# Sheet1.net
KiCad netlist of a schematic drawn in Altium Designer
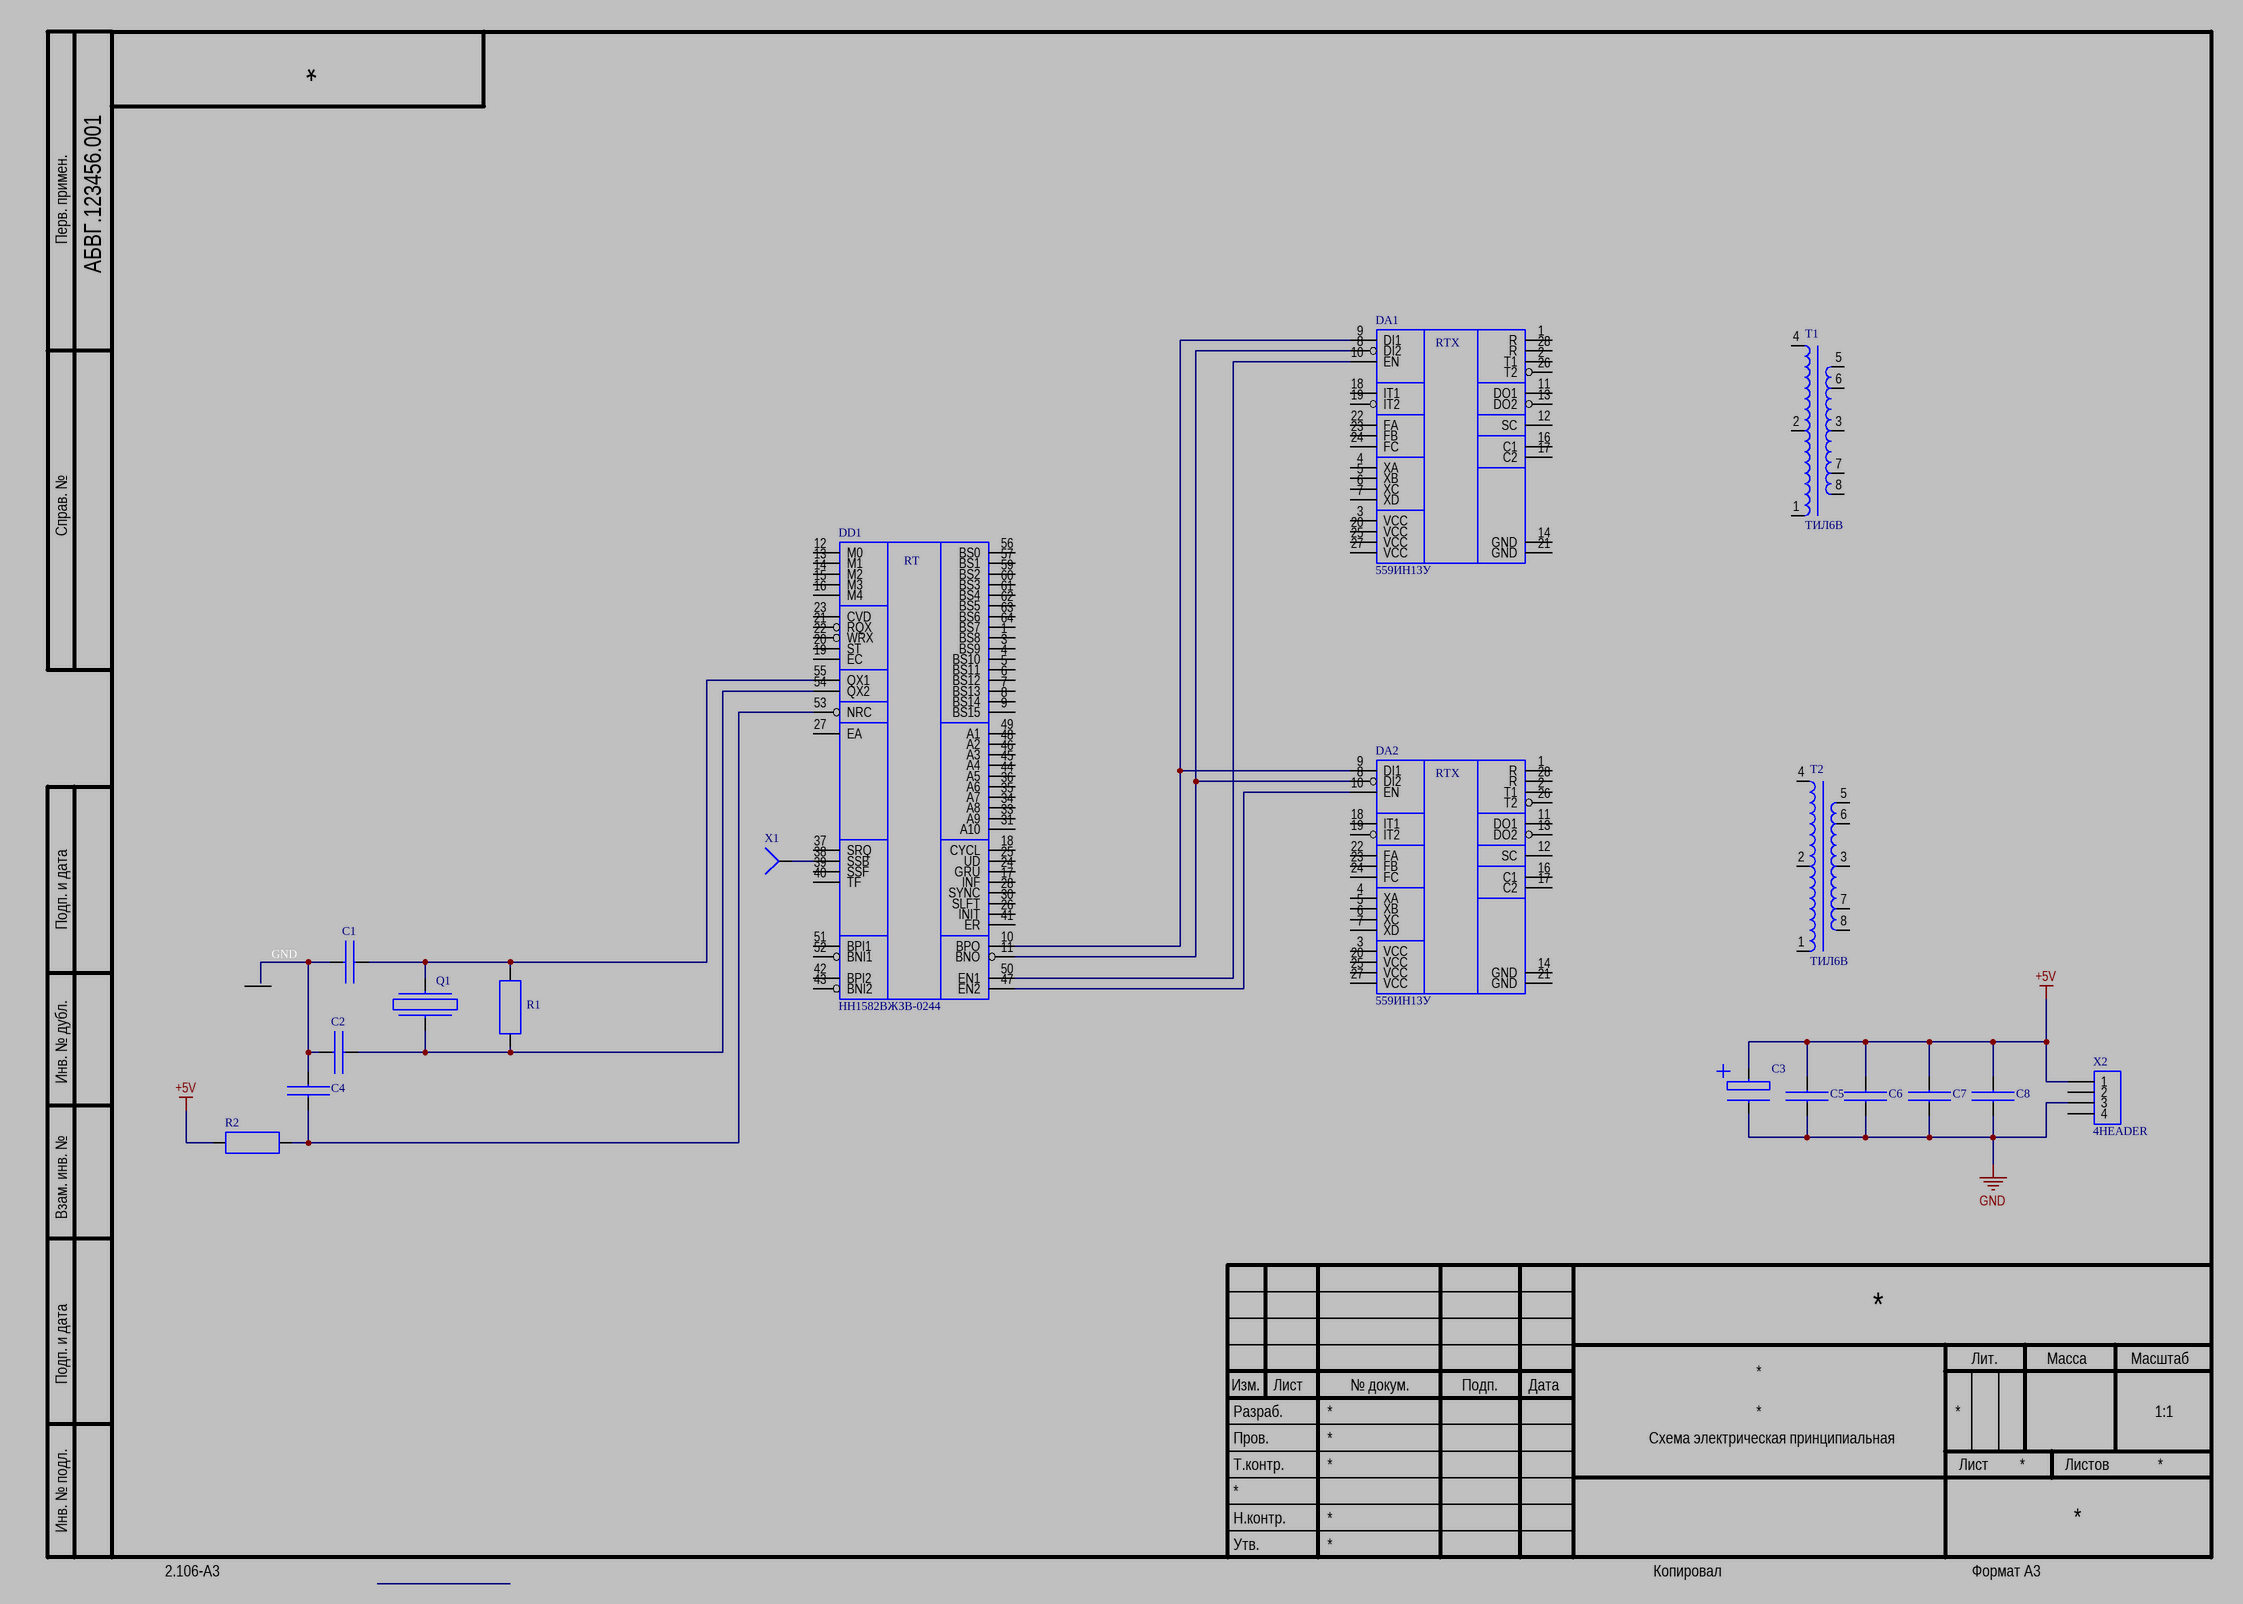
[diagram p0: Sheet1.SchDoc]

(export (version "E")
  (design (tool "Eeschema 10.0.6"))
  (components
    (comp (ref "C1") (value "C_2") (libsource (lib "Schlib1") (part "C_2")))
    (comp (ref "C2") (value "C_2") (libsource (lib "Schlib1") (part "C_2")))
    (comp (ref "C3") (value "C_3") (libsource (lib "Schlib1") (part "C_3")))
    (comp (ref "C4") (value "C_2") (libsource (lib "Schlib1") (part "C_2")))
    (comp (ref "C5") (value "C_2") (libsource (lib "Schlib1") (part "C_2")))
    (comp (ref "C6") (value "C_2") (libsource (lib "Schlib1") (part "C_2")))
    (comp (ref "C7") (value "C_2") (libsource (lib "Schlib1") (part "C_2")))
    (comp (ref "C8") (value "C_2") (libsource (lib "Schlib1") (part "C_2")))
    (comp (ref "DA1")
      (value "559ИН13У")
      (footprint "PcbLib1:H09.28-1B")
      (libsource (lib "Schlib1") (part "559ИН13У"))
    )
    (comp (ref "DA2")
      (value "559ИН13У")
      (footprint "PcbLib1:H09.28-1B")
      (libsource (lib "Schlib1") (part "559ИН13У"))
    )
    (comp (ref "DD1")
      (value "НН1582ВЖЗВ-0244")
      (footprint "PcbLib1:H18.64-1B")
      (libsource (lib "Schlib1") (part "НН1582ВЖЗВ-0244"))
    )
    (comp (ref "Q1") (value "Q_1") (libsource (lib "Schlib1") (part "Q_1")))
    (comp (ref "R1") (value "R_1") (libsource (lib "Schlib1") (part "R_1")))
    (comp (ref "R2") (value "100k") (libsource (lib "Schlib1") (part "R_1")))
    (comp (ref "T1") (value "ТИЛ6B") (libsource (lib "Schlib1") (part "ТИЛ6B")))
    (comp (ref "T2") (value "ТИЛ6B") (libsource (lib "Schlib1") (part "ТИЛ6B")))
    (comp (ref "X1") (value "X_5") (libsource (lib "Schlib1") (part "X_5")))
    (comp (ref "X2") (value "4HEADER") (libsource (lib "Schlib1") (part "4HEADER")))
  )
  (nets
    (net (code "1") (name "+5V") (class "Default")
      (node (ref "C3") (pin "1") (pintype "passive"))
      (node (ref "C5") (pin "2") (pintype "passive"))
      (node (ref "C6") (pin "2") (pintype "passive"))
      (node (ref "C7") (pin "2") (pintype "passive"))
      (node (ref "C8") (pin "2") (pintype "passive"))
      (node (ref "R2") (pin "1") (pintype "passive"))
      (node (ref "X2") (pin "1") (pinfunction "1_1") (pintype "passive"))
    )
    (net (code "2") (name "GND") (class "Default")
      (node (ref "C1") (pin "1") (pintype "passive"))
      (node (ref "C2") (pin "1") (pintype "passive"))
      (node (ref "C3") (pin "2") (pintype "passive"))
      (node (ref "C4") (pin "2") (pintype "passive"))
      (node (ref "C5") (pin "1") (pintype "passive"))
      (node (ref "C6") (pin "1") (pintype "passive"))
      (node (ref "C7") (pin "1") (pintype "passive"))
      (node (ref "C8") (pin "1") (pintype "passive"))
      (node (ref "X2") (pin "3") (pinfunction "3_3") (pintype "passive"))
    )
    (net (code "3") (name "Net-(DA1-DI1)") (class "Default")
      (node (ref "DA1") (pin "9") (pinfunction "DI1_9") (pintype "passive"))
      (node (ref "DA2") (pin "9") (pinfunction "DI1_9") (pintype "passive"))
      (node (ref "DD1") (pin "10") (pinfunction "BPO_10") (pintype "passive"))
    )
    (net (code "4") (name "Net-(DA1-DI2)") (class "Default")
      (node (ref "DA1") (pin "8") (pinfunction "DI2_8") (pintype "passive"))
      (node (ref "DA2") (pin "8") (pinfunction "DI2_8") (pintype "passive"))
      (node (ref "DD1") (pin "11") (pinfunction "BNO_11") (pintype "passive"))
    )
    (net (code "5") (name "Net-(DA1-EN)") (class "Default")
      (node (ref "DA1") (pin "10") (pinfunction "EN_10") (pintype "passive"))
      (node (ref "DD1") (pin "50") (pinfunction "EN1_50") (pintype "passive"))
    )
    (net (code "6") (name "Net-(DA2-EN)") (class "Default")
      (node (ref "DA2") (pin "10") (pinfunction "EN_10") (pintype "passive"))
      (node (ref "DD1") (pin "47") (pinfunction "EN2_47") (pintype "passive"))
    )
    (net (code "7") (name "Net-(DD1-NRC)") (class "Default")
      (node (ref "C4") (pin "1") (pintype "passive"))
      (node (ref "DD1") (pin "53") (pinfunction "NRC_53") (pintype "passive"))
      (node (ref "R2") (pin "2") (pintype "passive"))
    )
    (net (code "8") (name "Net-(DD1-QX1)") (class "Default")
      (node (ref "C1") (pin "2") (pintype "passive"))
      (node (ref "DD1") (pin "55") (pinfunction "QX1_55") (pintype "passive"))
      (node (ref "Q1") (pin "2") (pintype "passive"))
      (node (ref "R1") (pin "2") (pintype "passive"))
    )
    (net (code "9") (name "Net-(DD1-QX2)") (class "Default")
      (node (ref "C2") (pin "2") (pintype "passive"))
      (node (ref "DD1") (pin "54") (pinfunction "QX2_54") (pintype "passive"))
      (node (ref "Q1") (pin "1") (pintype "passive"))
      (node (ref "R1") (pin "1") (pintype "passive"))
    )
    (net (code "10") (name "Net-(DD1-SSB)") (class "Default")
      (node (ref "DD1") (pin "38") (pinfunction "SSB_38") (pintype "passive"))
      (node (ref "X1") (pin "1") (pintype "passive"))
    )
    (net (code "11") (name "unconnected-(DA1-C1-Pad16)") (class "Default")
      (node (ref "DA1") (pin "16") (pinfunction "C1_16") (pintype "passive"))
    )
    (net (code "12") (name "unconnected-(DA1-C2-Pad17)") (class "Default")
      (node (ref "DA1") (pin "17") (pinfunction "C2_17") (pintype "passive"))
    )
    (net (code "13") (name "unconnected-(DA1-DO1-Pad11)") (class "Default")
      (node (ref "DA1") (pin "11") (pinfunction "DO1_11") (pintype "passive"))
    )
    (net (code "14") (name "unconnected-(DA1-DO2-Pad13)") (class "Default")
      (node (ref "DA1") (pin "13") (pinfunction "DO2_13") (pintype "passive"))
    )
    (net (code "15") (name "unconnected-(DA1-FA-Pad22)") (class "Default")
      (node (ref "DA1") (pin "22") (pinfunction "FA_22") (pintype "passive"))
    )
    (net (code "16") (name "unconnected-(DA1-FB-Pad23)") (class "Default")
      (node (ref "DA1") (pin "23") (pinfunction "FB_23") (pintype "passive"))
    )
    (net (code "17") (name "unconnected-(DA1-FC-Pad24)") (class "Default")
      (node (ref "DA1") (pin "24") (pinfunction "FC_24") (pintype "passive"))
    )
    (net (code "18") (name "unconnected-(DA1-GND-Pad14)") (class "Default")
      (node (ref "DA1") (pin "14") (pinfunction "GND_14") (pintype "passive"))
    )
    (net (code "19") (name "unconnected-(DA1-GND-Pad21)") (class "Default")
      (node (ref "DA1") (pin "21") (pinfunction "GND_21") (pintype "passive"))
    )
    (net (code "20") (name "unconnected-(DA1-IT1-Pad18)") (class "Default")
      (node (ref "DA1") (pin "18") (pinfunction "IT1_18") (pintype "passive"))
    )
    (net (code "21") (name "unconnected-(DA1-IT2-Pad19)") (class "Default")
      (node (ref "DA1") (pin "19") (pinfunction "IT2_19") (pintype "passive"))
    )
    (net (code "22") (name "unconnected-(DA1-R-Pad1)") (class "Default")
      (node (ref "DA1") (pin "1") (pinfunction "R_1") (pintype "passive"))
    )
    (net (code "23") (name "unconnected-(DA1-R-Pad28)") (class "Default")
      (node (ref "DA1") (pin "28") (pinfunction "R_28") (pintype "passive"))
    )
    (net (code "24") (name "unconnected-(DA1-SC-Pad12)") (class "Default")
      (node (ref "DA1") (pin "12") (pinfunction "SC_12") (pintype "passive"))
    )
    (net (code "25") (name "unconnected-(DA1-T1-Pad2)") (class "Default")
      (node (ref "DA1") (pin "2") (pinfunction "T1_2") (pintype "passive"))
    )
    (net (code "26") (name "unconnected-(DA1-T2-Pad26)") (class "Default")
      (node (ref "DA1") (pin "26") (pinfunction "T2_26") (pintype "passive"))
    )
    (net (code "27") (name "unconnected-(DA1-VCC-Pad3)") (class "Default")
      (node (ref "DA1") (pin "3") (pinfunction "VCC_3") (pintype "passive"))
    )
    (net (code "28") (name "unconnected-(DA1-VCC-Pad20)") (class "Default")
      (node (ref "DA1") (pin "20") (pinfunction "VCC_20") (pintype "passive"))
    )
    (net (code "29") (name "unconnected-(DA1-VCC-Pad25)") (class "Default")
      (node (ref "DA1") (pin "25") (pinfunction "VCC_25") (pintype "passive"))
    )
    (net (code "30") (name "unconnected-(DA1-VCC-Pad27)") (class "Default")
      (node (ref "DA1") (pin "27") (pinfunction "VCC_27") (pintype "passive"))
    )
    (net (code "31") (name "unconnected-(DA1-XA-Pad4)") (class "Default")
      (node (ref "DA1") (pin "4") (pinfunction "XA_4") (pintype "passive"))
    )
    (net (code "32") (name "unconnected-(DA1-XB-Pad5)") (class "Default")
      (node (ref "DA1") (pin "5") (pinfunction "XB_5") (pintype "passive"))
    )
    (net (code "33") (name "unconnected-(DA1-XC-Pad6)") (class "Default")
      (node (ref "DA1") (pin "6") (pinfunction "XC_6") (pintype "passive"))
    )
    (net (code "34") (name "unconnected-(DA1-XD-Pad7)") (class "Default")
      (node (ref "DA1") (pin "7") (pinfunction "XD_7") (pintype "passive"))
    )
    (net (code "35") (name "unconnected-(DA2-C1-Pad16)") (class "Default")
      (node (ref "DA2") (pin "16") (pinfunction "C1_16") (pintype "passive"))
    )
    (net (code "36") (name "unconnected-(DA2-C2-Pad17)") (class "Default")
      (node (ref "DA2") (pin "17") (pinfunction "C2_17") (pintype "passive"))
    )
    (net (code "37") (name "unconnected-(DA2-DO1-Pad11)") (class "Default")
      (node (ref "DA2") (pin "11") (pinfunction "DO1_11") (pintype "passive"))
    )
    (net (code "38") (name "unconnected-(DA2-DO2-Pad13)") (class "Default")
      (node (ref "DA2") (pin "13") (pinfunction "DO2_13") (pintype "passive"))
    )
    (net (code "39") (name "unconnected-(DA2-FA-Pad22)") (class "Default")
      (node (ref "DA2") (pin "22") (pinfunction "FA_22") (pintype "passive"))
    )
    (net (code "40") (name "unconnected-(DA2-FB-Pad23)") (class "Default")
      (node (ref "DA2") (pin "23") (pinfunction "FB_23") (pintype "passive"))
    )
    (net (code "41") (name "unconnected-(DA2-FC-Pad24)") (class "Default")
      (node (ref "DA2") (pin "24") (pinfunction "FC_24") (pintype "passive"))
    )
    (net (code "42") (name "unconnected-(DA2-GND-Pad14)") (class "Default")
      (node (ref "DA2") (pin "14") (pinfunction "GND_14") (pintype "passive"))
    )
    (net (code "43") (name "unconnected-(DA2-GND-Pad21)") (class "Default")
      (node (ref "DA2") (pin "21") (pinfunction "GND_21") (pintype "passive"))
    )
    (net (code "44") (name "unconnected-(DA2-IT1-Pad18)") (class "Default")
      (node (ref "DA2") (pin "18") (pinfunction "IT1_18") (pintype "passive"))
    )
    (net (code "45") (name "unconnected-(DA2-IT2-Pad19)") (class "Default")
      (node (ref "DA2") (pin "19") (pinfunction "IT2_19") (pintype "passive"))
    )
    (net (code "46") (name "unconnected-(DA2-R-Pad1)") (class "Default")
      (node (ref "DA2") (pin "1") (pinfunction "R_1") (pintype "passive"))
    )
    (net (code "47") (name "unconnected-(DA2-R-Pad28)") (class "Default")
      (node (ref "DA2") (pin "28") (pinfunction "R_28") (pintype "passive"))
    )
    (net (code "48") (name "unconnected-(DA2-SC-Pad12)") (class "Default")
      (node (ref "DA2") (pin "12") (pinfunction "SC_12") (pintype "passive"))
    )
    (net (code "49") (name "unconnected-(DA2-T1-Pad2)") (class "Default")
      (node (ref "DA2") (pin "2") (pinfunction "T1_2") (pintype "passive"))
    )
    (net (code "50") (name "unconnected-(DA2-T2-Pad26)") (class "Default")
      (node (ref "DA2") (pin "26") (pinfunction "T2_26") (pintype "passive"))
    )
    (net (code "51") (name "unconnected-(DA2-VCC-Pad3)") (class "Default")
      (node (ref "DA2") (pin "3") (pinfunction "VCC_3") (pintype "passive"))
    )
    (net (code "52") (name "unconnected-(DA2-VCC-Pad20)") (class "Default")
      (node (ref "DA2") (pin "20") (pinfunction "VCC_20") (pintype "passive"))
    )
    (net (code "53") (name "unconnected-(DA2-VCC-Pad25)") (class "Default")
      (node (ref "DA2") (pin "25") (pinfunction "VCC_25") (pintype "passive"))
    )
    (net (code "54") (name "unconnected-(DA2-VCC-Pad27)") (class "Default")
      (node (ref "DA2") (pin "27") (pinfunction "VCC_27") (pintype "passive"))
    )
    (net (code "55") (name "unconnected-(DA2-XA-Pad4)") (class "Default")
      (node (ref "DA2") (pin "4") (pinfunction "XA_4") (pintype "passive"))
    )
    (net (code "56") (name "unconnected-(DA2-XB-Pad5)") (class "Default")
      (node (ref "DA2") (pin "5") (pinfunction "XB_5") (pintype "passive"))
    )
    (net (code "57") (name "unconnected-(DA2-XC-Pad6)") (class "Default")
      (node (ref "DA2") (pin "6") (pinfunction "XC_6") (pintype "passive"))
    )
    (net (code "58") (name "unconnected-(DA2-XD-Pad7)") (class "Default")
      (node (ref "DA2") (pin "7") (pinfunction "XD_7") (pintype "passive"))
    )
    (net (code "59") (name "unconnected-(DD1-A1-Pad49)") (class "Default")
      (node (ref "DD1") (pin "49") (pinfunction "A1_49") (pintype "passive"))
    )
    (net (code "60") (name "unconnected-(DD1-A2-Pad48)") (class "Default")
      (node (ref "DD1") (pin "48") (pinfunction "A2_48") (pintype "passive"))
    )
    (net (code "61") (name "unconnected-(DD1-A3-Pad46)") (class "Default")
      (node (ref "DD1") (pin "46") (pinfunction "A3_46") (pintype "passive"))
    )
    (net (code "62") (name "unconnected-(DD1-A4-Pad45)") (class "Default")
      (node (ref "DD1") (pin "45") (pinfunction "A4_45") (pintype "passive"))
    )
    (net (code "63") (name "unconnected-(DD1-A5-Pad44)") (class "Default")
      (node (ref "DD1") (pin "44") (pinfunction "A5_44") (pintype "passive"))
    )
    (net (code "64") (name "unconnected-(DD1-A6-Pad36)") (class "Default")
      (node (ref "DD1") (pin "36") (pinfunction "A6_36") (pintype "passive"))
    )
    (net (code "65") (name "unconnected-(DD1-A7-Pad35)") (class "Default")
      (node (ref "DD1") (pin "35") (pinfunction "A7_35") (pintype "passive"))
    )
    (net (code "66") (name "unconnected-(DD1-A8-Pad34)") (class "Default")
      (node (ref "DD1") (pin "34") (pinfunction "A8_34") (pintype "passive"))
    )
    (net (code "67") (name "unconnected-(DD1-A9-Pad33)") (class "Default")
      (node (ref "DD1") (pin "33") (pinfunction "A9_33") (pintype "passive"))
    )
    (net (code "68") (name "unconnected-(DD1-A10-Pad31)") (class "Default")
      (node (ref "DD1") (pin "31") (pinfunction "A10_31") (pintype "passive"))
    )
    (net (code "69") (name "unconnected-(DD1-BNI1-Pad52)") (class "Default")
      (node (ref "DD1") (pin "52") (pinfunction "BNI1_52") (pintype "passive"))
    )
    (net (code "70") (name "unconnected-(DD1-BNI2-Pad43)") (class "Default")
      (node (ref "DD1") (pin "43") (pinfunction "BNI2_43") (pintype "passive"))
    )
    (net (code "71") (name "unconnected-(DD1-BPI1-Pad51)") (class "Default")
      (node (ref "DD1") (pin "51") (pinfunction "BPI1_51") (pintype "passive"))
    )
    (net (code "72") (name "unconnected-(DD1-BPI2-Pad42)") (class "Default")
      (node (ref "DD1") (pin "42") (pinfunction "BPI2_42") (pintype "passive"))
    )
    (net (code "73") (name "unconnected-(DD1-BS0-Pad56)") (class "Default")
      (node (ref "DD1") (pin "56") (pinfunction "BS0_56") (pintype "passive"))
    )
    (net (code "74") (name "unconnected-(DD1-BS1-Pad57)") (class "Default")
      (node (ref "DD1") (pin "57") (pinfunction "BS1_57") (pintype "passive"))
    )
    (net (code "75") (name "unconnected-(DD1-BS2-Pad59)") (class "Default")
      (node (ref "DD1") (pin "59") (pinfunction "BS2_59") (pintype "passive"))
    )
    (net (code "76") (name "unconnected-(DD1-BS3-Pad60)") (class "Default")
      (node (ref "DD1") (pin "60") (pinfunction "BS3_60") (pintype "passive"))
    )
    (net (code "77") (name "unconnected-(DD1-BS4-Pad61)") (class "Default")
      (node (ref "DD1") (pin "61") (pinfunction "BS4_61") (pintype "passive"))
    )
    (net (code "78") (name "unconnected-(DD1-BS5-Pad62)") (class "Default")
      (node (ref "DD1") (pin "62") (pinfunction "BS5_62") (pintype "passive"))
    )
    (net (code "79") (name "unconnected-(DD1-BS6-Pad63)") (class "Default")
      (node (ref "DD1") (pin "63") (pinfunction "BS6_63") (pintype "passive"))
    )
    (net (code "80") (name "unconnected-(DD1-BS7-Pad64)") (class "Default")
      (node (ref "DD1") (pin "64") (pinfunction "BS7_64") (pintype "passive"))
    )
    (net (code "81") (name "unconnected-(DD1-BS8-Pad1)") (class "Default")
      (node (ref "DD1") (pin "1") (pinfunction "BS8_1") (pintype "passive"))
    )
    (net (code "82") (name "unconnected-(DD1-BS9-Pad3)") (class "Default")
      (node (ref "DD1") (pin "3") (pinfunction "BS9_3") (pintype "passive"))
    )
    (net (code "83") (name "unconnected-(DD1-BS10-Pad4)") (class "Default")
      (node (ref "DD1") (pin "4") (pinfunction "BS10_4") (pintype "passive"))
    )
    (net (code "84") (name "unconnected-(DD1-BS11-Pad5)") (class "Default")
      (node (ref "DD1") (pin "5") (pinfunction "BS11_5") (pintype "passive"))
    )
    (net (code "85") (name "unconnected-(DD1-BS12-Pad6)") (class "Default")
      (node (ref "DD1") (pin "6") (pinfunction "BS12_6") (pintype "passive"))
    )
    (net (code "86") (name "unconnected-(DD1-BS13-Pad7)") (class "Default")
      (node (ref "DD1") (pin "7") (pinfunction "BS13_7") (pintype "passive"))
    )
    (net (code "87") (name "unconnected-(DD1-BS14-Pad8)") (class "Default")
      (node (ref "DD1") (pin "8") (pinfunction "BS14_8") (pintype "passive"))
    )
    (net (code "88") (name "unconnected-(DD1-BS15-Pad9)") (class "Default")
      (node (ref "DD1") (pin "9") (pinfunction "BS15_9") (pintype "passive"))
    )
    (net (code "89") (name "unconnected-(DD1-CVD-Pad23)") (class "Default")
      (node (ref "DD1") (pin "23") (pinfunction "CVD_23") (pintype "passive"))
    )
    (net (code "90") (name "unconnected-(DD1-CYCL-Pad18)") (class "Default")
      (node (ref "DD1") (pin "18") (pinfunction "CYCL_18") (pintype "passive"))
    )
    (net (code "91") (name "unconnected-(DD1-EA-Pad27)") (class "Default")
      (node (ref "DD1") (pin "27") (pinfunction "EA_27") (pintype "passive"))
    )
    (net (code "92") (name "unconnected-(DD1-EC-Pad19)") (class "Default")
      (node (ref "DD1") (pin "19") (pinfunction "EC_19") (pintype "passive"))
    )
    (net (code "93") (name "unconnected-(DD1-ER-Pad41)") (class "Default")
      (node (ref "DD1") (pin "41") (pinfunction "ER_41") (pintype "passive"))
    )
    (net (code "94") (name "unconnected-(DD1-GRU-Pad24)") (class "Default")
      (node (ref "DD1") (pin "24") (pinfunction "GRU_24") (pintype "passive"))
    )
    (net (code "95") (name "unconnected-(DD1-INF-Pad17)") (class "Default")
      (node (ref "DD1") (pin "17") (pinfunction "INF_17") (pintype "passive"))
    )
    (net (code "96") (name "unconnected-(DD1-INIT-Pad26)") (class "Default")
      (node (ref "DD1") (pin "26") (pinfunction "INIT_26") (pintype "passive"))
    )
    (net (code "97") (name "unconnected-(DD1-M0-Pad12)") (class "Default")
      (node (ref "DD1") (pin "12") (pinfunction "M0_12") (pintype "passive"))
    )
    (net (code "98") (name "unconnected-(DD1-M1-Pad13)") (class "Default")
      (node (ref "DD1") (pin "13") (pinfunction "M1_13") (pintype "passive"))
    )
    (net (code "99") (name "unconnected-(DD1-M2-Pad14)") (class "Default")
      (node (ref "DD1") (pin "14") (pinfunction "M2_14") (pintype "passive"))
    )
    (net (code "100") (name "unconnected-(DD1-M3-Pad15)") (class "Default")
      (node (ref "DD1") (pin "15") (pinfunction "M3_15") (pintype "passive"))
    )
    (net (code "101") (name "unconnected-(DD1-M4-Pad16)") (class "Default")
      (node (ref "DD1") (pin "16") (pinfunction "M4_16") (pintype "passive"))
    )
    (net (code "102") (name "unconnected-(DD1-RQX-Pad21)") (class "Default")
      (node (ref "DD1") (pin "21") (pinfunction "RQX_21") (pintype "passive"))
    )
    (net (code "103") (name "unconnected-(DD1-SLFT-Pad30)") (class "Default")
      (node (ref "DD1") (pin "30") (pinfunction "SLFT_30") (pintype "passive"))
    )
    (net (code "104") (name "unconnected-(DD1-SRQ-Pad37)") (class "Default")
      (node (ref "DD1") (pin "37") (pinfunction "SRQ_37") (pintype "passive"))
    )
    (net (code "105") (name "unconnected-(DD1-SSF-Pad39)") (class "Default")
      (node (ref "DD1") (pin "39") (pinfunction "SSF_39") (pintype "passive"))
    )
    (net (code "106") (name "unconnected-(DD1-ST-Pad20)") (class "Default")
      (node (ref "DD1") (pin "20") (pinfunction "ST_20") (pintype "passive"))
    )
    (net (code "107") (name "unconnected-(DD1-SYNC-Pad28)") (class "Default")
      (node (ref "DD1") (pin "28") (pinfunction "SYNC_28") (pintype "passive"))
    )
    (net (code "108") (name "unconnected-(DD1-TF-Pad40)") (class "Default")
      (node (ref "DD1") (pin "40") (pinfunction "TF_40") (pintype "passive"))
    )
    (net (code "109") (name "unconnected-(DD1-UD-Pad25)") (class "Default")
      (node (ref "DD1") (pin "25") (pinfunction "UD_25") (pintype "passive"))
    )
    (net (code "110") (name "unconnected-(DD1-WRX-Pad22)") (class "Default")
      (node (ref "DD1") (pin "22") (pinfunction "WRX_22") (pintype "passive"))
    )
    (net (code "111") (name "unconnected-(T1-Pad1)") (class "Default")
      (node (ref "T1") (pin "1") (pintype "passive"))
    )
    (net (code "112") (name "unconnected-(T1-Pad2)") (class "Default")
      (node (ref "T1") (pin "2") (pintype "passive"))
    )
    (net (code "113") (name "unconnected-(T1-Pad3)") (class "Default")
      (node (ref "T1") (pin "3") (pintype "passive"))
    )
    (net (code "114") (name "unconnected-(T1-Pad4)") (class "Default")
      (node (ref "T1") (pin "4") (pintype "passive"))
    )
    (net (code "115") (name "unconnected-(T1-Pad5)") (class "Default")
      (node (ref "T1") (pin "5") (pintype "passive"))
    )
    (net (code "116") (name "unconnected-(T1-Pad6)") (class "Default")
      (node (ref "T1") (pin "6") (pintype "passive"))
    )
    (net (code "117") (name "unconnected-(T1-Pad7)") (class "Default")
      (node (ref "T1") (pin "7") (pintype "passive"))
    )
    (net (code "118") (name "unconnected-(T1-Pad8)") (class "Default")
      (node (ref "T1") (pin "8") (pintype "passive"))
    )
    (net (code "119") (name "unconnected-(T2-Pad1)") (class "Default")
      (node (ref "T2") (pin "1") (pintype "passive"))
    )
    (net (code "120") (name "unconnected-(T2-Pad2)") (class "Default")
      (node (ref "T2") (pin "2") (pintype "passive"))
    )
    (net (code "121") (name "unconnected-(T2-Pad3)") (class "Default")
      (node (ref "T2") (pin "3") (pintype "passive"))
    )
    (net (code "122") (name "unconnected-(T2-Pad4)") (class "Default")
      (node (ref "T2") (pin "4") (pintype "passive"))
    )
    (net (code "123") (name "unconnected-(T2-Pad5)") (class "Default")
      (node (ref "T2") (pin "5") (pintype "passive"))
    )
    (net (code "124") (name "unconnected-(T2-Pad6)") (class "Default")
      (node (ref "T2") (pin "6") (pintype "passive"))
    )
    (net (code "125") (name "unconnected-(T2-Pad7)") (class "Default")
      (node (ref "T2") (pin "7") (pintype "passive"))
    )
    (net (code "126") (name "unconnected-(T2-Pad8)") (class "Default")
      (node (ref "T2") (pin "8") (pintype "passive"))
    )
    (net (code "127") (name "unconnected-(X2-Pad2)") (class "Default")
      (node (ref "X2") (pin "2") (pinfunction "2_2") (pintype "passive"))
    )
    (net (code "128") (name "unconnected-(X2-Pad4)") (class "Default")
      (node (ref "X2") (pin "4") (pinfunction "4_4") (pintype "passive"))
    )
  )
)
